# main.net
KiCad netlist of a schematic drawn in EAGLE
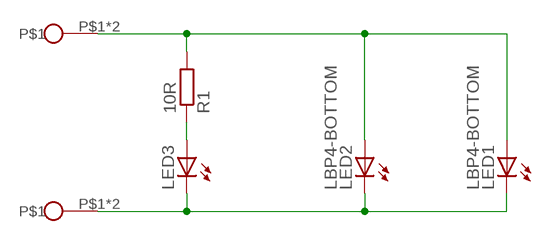
[diagram p0: schematic, sheet 1]

(export (version "E")
  (design (tool "Eeschema 10.0.6"))
  (components
    (comp (ref "GND")
      (value "BANANA-PLUG-2-PADS")
      (footprint "eagle-import:BANANA-PLUG-2-PADS")
      (libsource (lib "eagle-import") (part "BANANA-PLUG-2-PADS"))
    )
    (comp (ref "LED1")
      (value "LBP4-BOTTOM")
      (footprint "eagle-import:P47F-BOTTOM")
      (libsource (lib "eagle-import") (part "P4-BOTTOMLB"))
    )
    (comp (ref "LED2")
      (value "LBP4-BOTTOM")
      (footprint "eagle-import:P47F-BOTTOM")
      (libsource (lib "eagle-import") (part "P4-BOTTOMLB"))
    )
    (comp (ref "LED3")
      (value "LED3MM")
      (footprint "eagle-import:LED3MM")
      (libsource (lib "eagle-import") (part "LED3MM"))
    )
    (comp (ref "R1")
      (value "10R")
      (footprint "eagle-import:R1206")
      (libsource (lib "eagle-import") (part "R-EU_R1206"))
    )
    (comp (ref "U$1")
      (value "BANANA-PLUG-2-PADS")
      (footprint "eagle-import:BANANA-PLUG-2-PADS")
      (libsource (lib "eagle-import") (part "BANANA-PLUG-2-PADS"))
    )
  )
  (nets
    (net (code "1") (name "Net-(LED1-PadA)") (class "Default")
      (node (ref "LED1") (pin "A") (pinfunction "A_A") (pintype "passive"))
      (node (ref "LED2") (pin "A") (pinfunction "A_A") (pintype "passive"))
      (node (ref "R1") (pin "2") (pinfunction "2_2") (pintype "passive"))
      (node (ref "U$1") (pin "P$1") (pinfunction "P$1_P$1") (pintype "bidirectional"))
      (node (ref "U$1") (pin "P$2") (pinfunction "P$1_P$2") (pintype "bidirectional"))
    )
    (net (code "2") (name "Net-(LED3-C)") (class "Default")
      (node (ref "GND") (pin "P$1") (pinfunction "P$1_P$1") (pintype "bidirectional"))
      (node (ref "GND") (pin "P$2") (pinfunction "P$1_P$2") (pintype "bidirectional"))
      (node (ref "LED1") (pin "C") (pinfunction "C_C") (pintype "passive"))
      (node (ref "LED2") (pin "C") (pinfunction "C_C") (pintype "passive"))
      (node (ref "LED3") (pin "K") (pinfunction "C_K") (pintype "passive"))
    )
    (net (code "3") (name "Net-(LED3-PadA)") (class "Default")
      (node (ref "LED3") (pin "A") (pinfunction "A_A") (pintype "passive"))
      (node (ref "R1") (pin "1") (pinfunction "1_1") (pintype "passive"))
    )
  )
)
